# 40_INPUT_ROUTING.net
KiCad netlist of a schematic drawn in Altium Designer
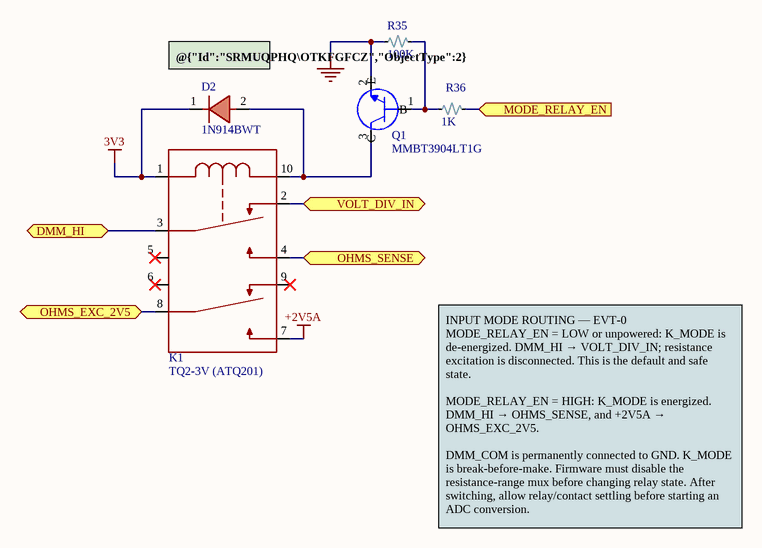
[diagram p0: 40_INPUT_ROUTING.SchDoc]

(export (version "E")
  (design (tool "Eeschema 10.0.6"))
  (components
    (comp (ref "D2")
      (value "1N914BWT")
      (footprint "1N914BWT")
      (description "DIODE STANDARD 75V 200MA SOD523F")
      (fields (field (name "MANUFACTURER") "onsemi"))
      (libsource (lib "PocketLab_DMM_EVT0") (part "1N914BWT"))
    )
    (comp (ref "K1")
      (value "TQ2-3V (ATQ201)")
      (footprint "TQ2-3V")
      (description "Electromechanical Relay Double Pole Double Throw 1A 3 Volt 64.3Ohm Through Hole")
      (fields (field (name "MANUFACTURER") "Panasonic") (field (name "MANUFACTURER PART NUMBER") "TQ2-3V"))
      (libsource (lib "PocketLab_DMM_EVT0") (part "TQ2-3V"))
    )
    (comp (ref "Q1")
      (value "MMBT3904LT1G")
      (footprint "MMBT3904")
      (description "TRANS NPN 40V 0.2A SOT23-3")
      (fields (field (name "MANUFACTURER") "onsemi"))
      (libsource (lib "PocketLab_DMM_EVT0") (part "MMBT3904LT1G"))
    )
    (comp (ref "R35")
      (value "100K")
      (footprint "R0805")
      (description "RES 1/8W 0805")
      (fields
        (field (name "MANUFACTURER") "Stackpole Electronics")
        (field (name "MANUFACTURER PART NUMBER") "RNCF0805TKY10K0")
      )
      (libsource (lib "PocketLab_DMM_EVT0") (part "R_0805"))
    )
    (comp (ref "R36")
      (value "1K")
      (footprint "R0805")
      (description "RES 1/8W 0805")
      (fields
        (field (name "MANUFACTURER") "Stackpole Electronics")
        (field (name "MANUFACTURER PART NUMBER") "RNCF0805TKY10K0")
      )
      (libsource (lib "PocketLab_DMM_EVT0") (part "R_0805"))
    )
  )
  (nets
    (net (code "1") (name "+2V5A") (class "Default")
      (node (ref "K1") (pin "7") (pinfunction "7_7") (pintype "passive"))
    )
    (net (code "2") (name "/DMM_HI") (class "Default")
      (node (ref "K1") (pin "3") (pinfunction "3_3") (pintype "passive"))
    )
    (net (code "3") (name "/MODE_RELAY_EN") (class "Default")
      (node (ref "R36") (pin "2") (pinfunction "2_2") (pintype "passive"))
    )
    (net (code "4") (name "/OHMS_EXC_2V5") (class "Default")
      (node (ref "K1") (pin "8") (pinfunction "8_8") (pintype "passive"))
    )
    (net (code "5") (name "/OHMS_SENSE") (class "Default")
      (node (ref "K1") (pin "4") (pinfunction "4_4") (pintype "passive"))
    )
    (net (code "6") (name "/VOLT_DIV_IN") (class "Default")
      (node (ref "K1") (pin "2") (pinfunction "2_2") (pintype "passive"))
    )
    (net (code "7") (name "3V3") (class "Default")
      (node (ref "D2") (pin "1") (pinfunction "cathode_1") (pintype "passive"))
      (node (ref "K1") (pin "1") (pinfunction "1_1") (pintype "passive"))
    )
    (net (code "8") (name "GND") (class "Default")
      (node (ref "Q1") (pin "2") (pinfunction "E_2") (pintype "passive"))
      (node (ref "R35") (pin "1") (pinfunction "1_1") (pintype "passive"))
    )
    (net (code "9") (name "Net-(D2-anode)") (class "Default")
      (node (ref "D2") (pin "2") (pinfunction "anode_2") (pintype "passive"))
      (node (ref "K1") (pin "10") (pinfunction "10_10") (pintype "passive"))
      (node (ref "Q1") (pin "3") (pinfunction "C_3") (pintype "passive"))
    )
    (net (code "10") (name "Net-(Q1-B)") (class "Default")
      (node (ref "Q1") (pin "1") (pinfunction "B_1") (pintype "passive"))
      (node (ref "R35") (pin "2") (pinfunction "2_2") (pintype "passive"))
      (node (ref "R36") (pin "1") (pinfunction "1_1") (pintype "passive"))
    )
    (net (code "11") (name "unconnected-(K1-Pad5)") (class "Default")
      (node (ref "K1") (pin "5") (pinfunction "5_5") (pintype "passive+no_connect"))
    )
    (net (code "12") (name "unconnected-(K1-Pad6)") (class "Default")
      (node (ref "K1") (pin "6") (pinfunction "6_6") (pintype "passive+no_connect"))
    )
    (net (code "13") (name "unconnected-(K1-Pad9)") (class "Default")
      (node (ref "K1") (pin "9") (pinfunction "9_9") (pintype "passive+no_connect"))
    )
  )
)
